# BaseArduino.net
KiCad netlist of a schematic drawn in Altium Designer
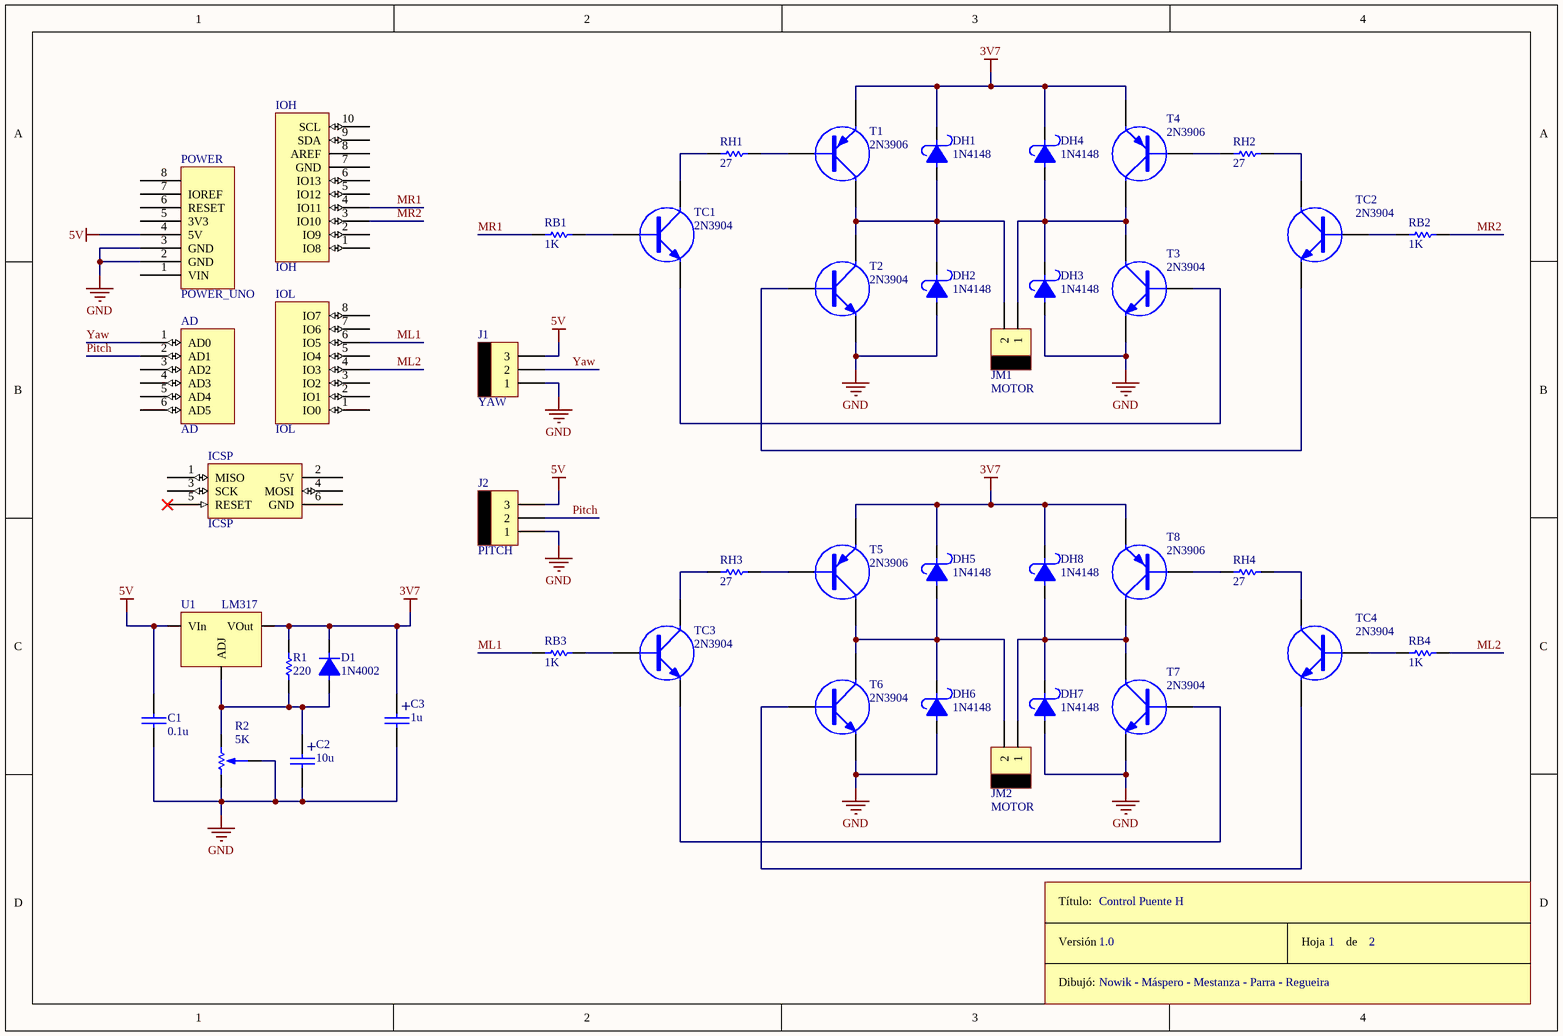
[diagram p0: BaseArduino.SchDoc]

(export (version "E")
  (design (tool "Eeschema 10.0.6"))
  (components
    (comp (ref "AD") (value "AD") (footprint "Header 6x1 8.5mm") (libsource (lib "Headers") (part "AD")))
    (comp (ref "C1") (value "0.1u") (footprint "CAP100") (libsource (lib "LIBEBAL") (part "CAP")))
    (comp (ref "C2") (value "10u") (footprint "CAP100RP") (libsource (lib "LIBEBAL") (part "CAPPOL")))
    (comp (ref "C3") (value "1u") (footprint "CAP100RP") (libsource (lib "LIBEBAL") (part "CAPPOL")))
    (comp (ref "D1") (value "1N4002") (footprint "DO41") (libsource (lib "LIBEBAL") (part "DIODO")))
    (comp (ref "DH1") (value "1N4148") (footprint "DO41") (libsource (lib "LIBEBAL") (part "DIODO SCHOTTKY")))
    (comp (ref "DH2") (value "1N4148") (footprint "DO41") (libsource (lib "LIBEBAL") (part "DIODO SCHOTTKY")))
    (comp (ref "DH3") (value "1N4148") (footprint "DO41") (libsource (lib "LIBEBAL") (part "DIODO SCHOTTKY")))
    (comp (ref "DH4") (value "1N4148") (footprint "DO41") (libsource (lib "LIBEBAL") (part "DIODO SCHOTTKY")))
    (comp (ref "DH5") (value "1N4148") (footprint "DO41") (libsource (lib "LIBEBAL") (part "DIODO SCHOTTKY")))
    (comp (ref "DH6") (value "1N4148") (footprint "DO41") (libsource (lib "LIBEBAL") (part "DIODO SCHOTTKY")))
    (comp (ref "DH7") (value "1N4148") (footprint "DO41") (libsource (lib "LIBEBAL") (part "DIODO SCHOTTKY")))
    (comp (ref "DH8") (value "1N4148") (footprint "DO41") (libsource (lib "LIBEBAL") (part "DIODO SCHOTTKY")))
    (comp (ref "ICSP") (value "ICSP") (footprint "ICSP") (libsource (lib "Headers") (part "ICSP")))
    (comp (ref "IOH") (value "IOH") (footprint "Header 10x1 8.5mm") (libsource (lib "Headers") (part "IOH")))
    (comp (ref "IOL") (value "IOL") (footprint "Header 8x1 8.5mm") (libsource (lib "Headers") (part "IOL")))
    (comp (ref "J1") (value "YAW") (footprint "MOLEX3") (libsource (lib "LIBEBAL") (part "MOLEX3")))
    (comp (ref "J2") (value "PITCH") (footprint "MOLEX3") (libsource (lib "LIBEBAL") (part "MOLEX3")))
    (comp (ref "JM1") (value "MOTOR") (footprint "MOLEX2") (libsource (lib "LIBEBAL") (part "MOLEX2")))
    (comp (ref "JM2") (value "MOTOR") (footprint "MOLEX2") (libsource (lib "LIBEBAL") (part "MOLEX2")))
    (comp (ref "POWER")
      (value "POWER_UNO")
      (footprint "Header 8x1 8.5mm")
      (libsource (lib "Headers") (part "POWER_UNO"))
    )
    (comp (ref "R1") (value "220") (footprint "RES300") (libsource (lib "LIBEBAL") (part "RES")))
    (comp (ref "R2") (value "5K") (footprint "PRESET V") (libsource (lib "LIBEBAL") (part "PRESET")))
    (comp (ref "RB1") (value "1K") (footprint "RES300") (libsource (lib "LIBEBAL") (part "RES")))
    (comp (ref "RB2") (value "1K") (footprint "RES300") (libsource (lib "LIBEBAL") (part "RES")))
    (comp (ref "RB3") (value "1K") (footprint "RES300") (libsource (lib "LIBEBAL") (part "RES")))
    (comp (ref "RB4") (value "1K") (footprint "RES300") (libsource (lib "LIBEBAL") (part "RES")))
    (comp (ref "RH1") (value "27") (footprint "RES300") (libsource (lib "LIBEBAL") (part "RES")))
    (comp (ref "RH2") (value "27") (footprint "RES300") (libsource (lib "LIBEBAL") (part "RES")))
    (comp (ref "RH3") (value "27") (footprint "RES300") (libsource (lib "LIBEBAL") (part "RES")))
    (comp (ref "RH4") (value "27") (footprint "RES300") (libsource (lib "LIBEBAL") (part "RES")))
    (comp (ref "ROT1") (value "Rótulo") (libsource (lib "LIB PIO IX") (part "Rótulo")))
    (comp (ref "T1") (value "2N3906") (footprint "TO92") (libsource (lib "LIBEBAL") (part "TRANSISTOR PNP")))
    (comp (ref "T2")
      (value "2N3904")
      (footprint "LIBEBAL:TO92")
      (libsource (lib "LIBEBAL") (part "TRANSISTOR NPN"))
    )
    (comp (ref "T3")
      (value "2N3904")
      (footprint "LIBEBAL:TO92")
      (libsource (lib "LIBEBAL") (part "TRANSISTOR NPN"))
    )
    (comp (ref "T4")
      (value "2N3906")
      (footprint "LIBEBAL:TO92")
      (libsource (lib "LIBEBAL") (part "TRANSISTOR PNP"))
    )
    (comp (ref "T5") (value "2N3906") (footprint "TO92") (libsource (lib "LIBEBAL") (part "TRANSISTOR PNP")))
    (comp (ref "T6") (value "2N3904") (footprint "TO92") (libsource (lib "LIBEBAL") (part "TRANSISTOR NPN")))
    (comp (ref "T7") (value "2N3904") (footprint "TO92") (libsource (lib "LIBEBAL") (part "TRANSISTOR NPN")))
    (comp (ref "T8") (value "2N3906") (footprint "TO92") (libsource (lib "LIBEBAL") (part "TRANSISTOR PNP")))
    (comp (ref "TC1") (value "2N3904") (footprint "TO92") (libsource (lib "LIBEBAL") (part "TRANSISTOR NPN")))
    (comp (ref "TC2")
      (value "2N3904")
      (footprint "LIBEBAL:TO92")
      (libsource (lib "LIBEBAL") (part "TRANSISTOR NPN"))
    )
    (comp (ref "TC3") (value "2N3904") (footprint "TO92") (libsource (lib "LIBEBAL") (part "TRANSISTOR NPN")))
    (comp (ref "TC4") (value "2N3904") (footprint "TO92") (libsource (lib "LIBEBAL") (part "TRANSISTOR NPN")))
    (comp (ref "U1")
      (value "LM317")
      (footprint "TO-220 V")
      (description "IC REG ADJ 1.5A 3 TERM TO-220")
      (libsource (lib "LIBEBAL") (part "LM317"))
    )
  )
  (nets
    (net (code "1") (name "/ML1") (class "Default")
      (node (ref "IOL") (pin "6") (pinfunction "IO5_6") (pintype "bidirectional"))
      (node (ref "RB3") (pin "1") (pinfunction "1_1") (pintype "passive"))
    )
    (net (code "2") (name "/ML2") (class "Default")
      (node (ref "IOL") (pin "4") (pinfunction "IO3_4") (pintype "bidirectional"))
      (node (ref "RB4") (pin "2") (pinfunction "2_2") (pintype "passive"))
    )
    (net (code "3") (name "/MR1") (class "Default")
      (node (ref "IOH") (pin "4") (pinfunction "IO11_4") (pintype "bidirectional"))
      (node (ref "RB1") (pin "1") (pinfunction "1_1") (pintype "passive"))
    )
    (net (code "4") (name "/MR2") (class "Default")
      (node (ref "IOH") (pin "3") (pinfunction "IO10_3") (pintype "bidirectional"))
      (node (ref "RB2") (pin "2") (pinfunction "2_2") (pintype "passive"))
    )
    (net (code "5") (name "/Pitch") (class "Default")
      (node (ref "AD") (pin "2") (pinfunction "AD1_2") (pintype "bidirectional"))
      (node (ref "J2") (pin "2") (pinfunction "2_2") (pintype "passive"))
    )
    (net (code "6") (name "/Yaw") (class "Default")
      (node (ref "AD") (pin "1") (pinfunction "AD0_1") (pintype "bidirectional"))
      (node (ref "J1") (pin "2") (pinfunction "2_2") (pintype "passive"))
    )
    (net (code "7") (name "3V7") (class "Default")
      (node (ref "C3") (pin "1") (pinfunction "1_1") (pintype "passive"))
      (node (ref "D1") (pin "2") (pinfunction "2_2") (pintype "passive"))
      (node (ref "DH1") (pin "2") (pinfunction "2_2") (pintype "passive"))
      (node (ref "DH4") (pin "2") (pinfunction "2_2") (pintype "passive"))
      (node (ref "DH5") (pin "2") (pinfunction "2_2") (pintype "passive"))
      (node (ref "DH8") (pin "2") (pinfunction "2_2") (pintype "passive"))
      (node (ref "R1") (pin "2") (pinfunction "2_2") (pintype "passive"))
      (node (ref "T1") (pin "3") (pinfunction "E_3") (pintype "passive"))
      (node (ref "T4") (pin "3") (pinfunction "E_3") (pintype "passive"))
      (node (ref "T5") (pin "3") (pinfunction "E_3") (pintype "passive"))
      (node (ref "T8") (pin "3") (pinfunction "E_3") (pintype "passive"))
      (node (ref "U1") (pin "2") (pinfunction "VOut_2") (pintype "passive"))
    )
    (net (code "8") (name "5V") (class "Default")
      (node (ref "C1") (pin "1") (pinfunction "1_1") (pintype "passive"))
      (node (ref "J1") (pin "3") (pinfunction "3_3") (pintype "passive"))
      (node (ref "J2") (pin "3") (pinfunction "3_3") (pintype "passive"))
      (node (ref "POWER") (pin "4") (pinfunction "5V_4") (pintype "power_in"))
      (node (ref "U1") (pin "3") (pinfunction "VIn_3") (pintype "passive"))
    )
    (net (code "9") (name "GND") (class "Default")
      (node (ref "C1") (pin "2") (pinfunction "2_2") (pintype "passive"))
      (node (ref "C2") (pin "2") (pinfunction "2_2") (pintype "passive"))
      (node (ref "C3") (pin "2") (pinfunction "2_2") (pintype "passive"))
      (node (ref "DH2") (pin "1") (pinfunction "1_1") (pintype "passive"))
      (node (ref "DH3") (pin "1") (pinfunction "1_1") (pintype "passive"))
      (node (ref "DH6") (pin "1") (pinfunction "1_1") (pintype "passive"))
      (node (ref "DH7") (pin "1") (pinfunction "1_1") (pintype "passive"))
      (node (ref "J1") (pin "1") (pinfunction "1_1") (pintype "passive"))
      (node (ref "J2") (pin "1") (pinfunction "1_1") (pintype "passive"))
      (node (ref "POWER") (pin "2") (pinfunction "GND_2") (pintype "power_in"))
      (node (ref "POWER") (pin "3") (pinfunction "GND_3") (pintype "power_in"))
      (node (ref "R2") (pin "2") (pinfunction "2_2") (pintype "passive"))
      (node (ref "R2") (pin "3") (pinfunction "3_3") (pintype "passive"))
      (node (ref "T2") (pin "3") (pinfunction "E_3") (pintype "passive"))
      (node (ref "T3") (pin "3") (pinfunction "E_3") (pintype "passive"))
      (node (ref "T6") (pin "3") (pinfunction "E_3") (pintype "passive"))
      (node (ref "T7") (pin "3") (pinfunction "E_3") (pintype "passive"))
    )
    (net (code "10") (name "Net-(T1-B)") (class "Default")
      (node (ref "RH1") (pin "2") (pinfunction "2_2") (pintype "passive"))
      (node (ref "T1") (pin "1") (pinfunction "B_1") (pintype "passive"))
    )
    (net (code "11") (name "Net-(T1-C)") (class "Default")
      (node (ref "DH1") (pin "1") (pinfunction "1_1") (pintype "passive"))
      (node (ref "DH2") (pin "2") (pinfunction "2_2") (pintype "passive"))
      (node (ref "JM1") (pin "2") (pinfunction "2_2") (pintype "passive"))
      (node (ref "T1") (pin "2") (pinfunction "C_2") (pintype "passive"))
      (node (ref "T2") (pin "2") (pinfunction "C_2") (pintype "passive"))
    )
    (net (code "12") (name "Net-(T2-B)") (class "Default")
      (node (ref "T2") (pin "1") (pinfunction "B_1") (pintype "passive"))
      (node (ref "TC2") (pin "3") (pinfunction "E_3") (pintype "passive"))
    )
    (net (code "13") (name "Net-(T3-B)") (class "Default")
      (node (ref "T3") (pin "1") (pinfunction "B_1") (pintype "passive"))
      (node (ref "TC1") (pin "3") (pinfunction "E_3") (pintype "passive"))
    )
    (net (code "14") (name "Net-(T3-C)") (class "Default")
      (node (ref "DH3") (pin "2") (pinfunction "2_2") (pintype "passive"))
      (node (ref "DH4") (pin "1") (pinfunction "1_1") (pintype "passive"))
      (node (ref "JM1") (pin "1") (pinfunction "1_1") (pintype "passive"))
      (node (ref "T3") (pin "2") (pinfunction "C_2") (pintype "passive"))
      (node (ref "T4") (pin "2") (pinfunction "C_2") (pintype "passive"))
    )
    (net (code "15") (name "Net-(T4-B)") (class "Default")
      (node (ref "RH2") (pin "1") (pinfunction "1_1") (pintype "passive"))
      (node (ref "T4") (pin "1") (pinfunction "B_1") (pintype "passive"))
    )
    (net (code "16") (name "Net-(T5-B)") (class "Default")
      (node (ref "RH3") (pin "2") (pinfunction "2_2") (pintype "passive"))
      (node (ref "T5") (pin "1") (pinfunction "B_1") (pintype "passive"))
    )
    (net (code "17") (name "Net-(T5-C)") (class "Default")
      (node (ref "DH5") (pin "1") (pinfunction "1_1") (pintype "passive"))
      (node (ref "DH6") (pin "2") (pinfunction "2_2") (pintype "passive"))
      (node (ref "JM2") (pin "2") (pinfunction "2_2") (pintype "passive"))
      (node (ref "T5") (pin "2") (pinfunction "C_2") (pintype "passive"))
      (node (ref "T6") (pin "2") (pinfunction "C_2") (pintype "passive"))
    )
    (net (code "18") (name "Net-(T6-B)") (class "Default")
      (node (ref "T6") (pin "1") (pinfunction "B_1") (pintype "passive"))
      (node (ref "TC4") (pin "3") (pinfunction "E_3") (pintype "passive"))
    )
    (net (code "19") (name "Net-(T7-B)") (class "Default")
      (node (ref "T7") (pin "1") (pinfunction "B_1") (pintype "passive"))
      (node (ref "TC3") (pin "3") (pinfunction "E_3") (pintype "passive"))
    )
    (net (code "20") (name "Net-(T7-C)") (class "Default")
      (node (ref "DH7") (pin "2") (pinfunction "2_2") (pintype "passive"))
      (node (ref "DH8") (pin "1") (pinfunction "1_1") (pintype "passive"))
      (node (ref "JM2") (pin "1") (pinfunction "1_1") (pintype "passive"))
      (node (ref "T7") (pin "2") (pinfunction "C_2") (pintype "passive"))
      (node (ref "T8") (pin "2") (pinfunction "C_2") (pintype "passive"))
    )
    (net (code "21") (name "Net-(T8-B)") (class "Default")
      (node (ref "RH4") (pin "1") (pinfunction "1_1") (pintype "passive"))
      (node (ref "T8") (pin "1") (pinfunction "B_1") (pintype "passive"))
    )
    (net (code "22") (name "Net-(TC1-B)") (class "Default")
      (node (ref "RB1") (pin "2") (pinfunction "2_2") (pintype "passive"))
      (node (ref "TC1") (pin "1") (pinfunction "B_1") (pintype "passive"))
    )
    (net (code "23") (name "Net-(TC1-C)") (class "Default")
      (node (ref "RH1") (pin "1") (pinfunction "1_1") (pintype "passive"))
      (node (ref "TC1") (pin "2") (pinfunction "C_2") (pintype "passive"))
    )
    (net (code "24") (name "Net-(TC2-B)") (class "Default")
      (node (ref "RB2") (pin "1") (pinfunction "1_1") (pintype "passive"))
      (node (ref "TC2") (pin "1") (pinfunction "B_1") (pintype "passive"))
    )
    (net (code "25") (name "Net-(TC2-C)") (class "Default")
      (node (ref "RH2") (pin "2") (pinfunction "2_2") (pintype "passive"))
      (node (ref "TC2") (pin "2") (pinfunction "C_2") (pintype "passive"))
    )
    (net (code "26") (name "Net-(TC3-B)") (class "Default")
      (node (ref "RB3") (pin "2") (pinfunction "2_2") (pintype "passive"))
      (node (ref "TC3") (pin "1") (pinfunction "B_1") (pintype "passive"))
    )
    (net (code "27") (name "Net-(TC3-C)") (class "Default")
      (node (ref "RH3") (pin "1") (pinfunction "1_1") (pintype "passive"))
      (node (ref "TC3") (pin "2") (pinfunction "C_2") (pintype "passive"))
    )
    (net (code "28") (name "Net-(TC4-B)") (class "Default")
      (node (ref "RB4") (pin "1") (pinfunction "1_1") (pintype "passive"))
      (node (ref "TC4") (pin "1") (pinfunction "B_1") (pintype "passive"))
    )
    (net (code "29") (name "Net-(TC4-C)") (class "Default")
      (node (ref "RH4") (pin "2") (pinfunction "2_2") (pintype "passive"))
      (node (ref "TC4") (pin "2") (pinfunction "C_2") (pintype "passive"))
    )
    (net (code "30") (name "Net-(U1-ADJ)") (class "Default")
      (node (ref "C2") (pin "1") (pinfunction "1_1") (pintype "passive"))
      (node (ref "D1") (pin "1") (pinfunction "1_1") (pintype "passive"))
      (node (ref "R1") (pin "1") (pinfunction "1_1") (pintype "passive"))
      (node (ref "R2") (pin "1") (pinfunction "1_1") (pintype "passive"))
      (node (ref "U1") (pin "1") (pinfunction "ADJ_1") (pintype "passive"))
    )
    (net (code "31") (name "unconnected-(AD-AD2-Pad3)") (class "Default")
      (node (ref "AD") (pin "3") (pinfunction "AD2_3") (pintype "bidirectional"))
    )
    (net (code "32") (name "unconnected-(AD-AD3-Pad4)") (class "Default")
      (node (ref "AD") (pin "4") (pinfunction "AD3_4") (pintype "bidirectional"))
    )
    (net (code "33") (name "unconnected-(AD-AD4-Pad5)") (class "Default")
      (node (ref "AD") (pin "5") (pinfunction "AD4_5") (pintype "bidirectional"))
    )
    (net (code "34") (name "unconnected-(AD-AD5-Pad6)") (class "Default")
      (node (ref "AD") (pin "6") (pinfunction "AD5_6") (pintype "bidirectional"))
    )
    (net (code "35") (name "unconnected-(ICSP-5V-Pad2)") (class "Default")
      (node (ref "ICSP") (pin "2") (pinfunction "5V_2") (pintype "power_in"))
    )
    (net (code "36") (name "unconnected-(ICSP-GND-Pad6)") (class "Default")
      (node (ref "ICSP") (pin "6") (pinfunction "GND_6") (pintype "power_in"))
    )
    (net (code "37") (name "unconnected-(ICSP-MISO-Pad1)") (class "Default")
      (node (ref "ICSP") (pin "1") (pinfunction "MISO_1") (pintype "bidirectional"))
    )
    (net (code "38") (name "unconnected-(ICSP-MOSI-Pad4)") (class "Default")
      (node (ref "ICSP") (pin "4") (pinfunction "MOSI_4") (pintype "bidirectional"))
    )
    (net (code "39") (name "unconnected-(ICSP-RESET-Pad5)") (class "Default")
      (node (ref "ICSP") (pin "5") (pinfunction "RESET_5") (pintype "input+no_connect"))
    )
    (net (code "40") (name "unconnected-(ICSP-SCK-Pad3)") (class "Default")
      (node (ref "ICSP") (pin "3") (pinfunction "SCK_3") (pintype "bidirectional"))
    )
    (net (code "41") (name "unconnected-(IOH-AREF-Pad8)") (class "Default")
      (node (ref "IOH") (pin "8") (pinfunction "AREF_8") (pintype "passive"))
    )
    (net (code "42") (name "unconnected-(IOH-GND-Pad7)") (class "Default")
      (node (ref "IOH") (pin "7") (pinfunction "GND_7") (pintype "power_in"))
    )
    (net (code "43") (name "unconnected-(IOH-IO8-Pad1)") (class "Default")
      (node (ref "IOH") (pin "1") (pinfunction "IO8_1") (pintype "bidirectional"))
    )
    (net (code "44") (name "unconnected-(IOH-IO9-Pad2)") (class "Default")
      (node (ref "IOH") (pin "2") (pinfunction "IO9_2") (pintype "bidirectional"))
    )
    (net (code "45") (name "unconnected-(IOH-IO12-Pad5)") (class "Default")
      (node (ref "IOH") (pin "5") (pinfunction "IO12_5") (pintype "bidirectional"))
    )
    (net (code "46") (name "unconnected-(IOH-IO13-Pad6)") (class "Default")
      (node (ref "IOH") (pin "6") (pinfunction "IO13_6") (pintype "bidirectional"))
    )
    (net (code "47") (name "unconnected-(IOH-SCL-Pad10)") (class "Default")
      (node (ref "IOH") (pin "10") (pinfunction "SCL_10") (pintype "bidirectional"))
    )
    (net (code "48") (name "unconnected-(IOH-SDA-Pad9)") (class "Default")
      (node (ref "IOH") (pin "9") (pinfunction "SDA_9") (pintype "bidirectional"))
    )
    (net (code "49") (name "unconnected-(IOL-IO0-Pad1)") (class "Default")
      (node (ref "IOL") (pin "1") (pinfunction "IO0_1") (pintype "bidirectional"))
    )
    (net (code "50") (name "unconnected-(IOL-IO1-Pad2)") (class "Default")
      (node (ref "IOL") (pin "2") (pinfunction "IO1_2") (pintype "bidirectional"))
    )
    (net (code "51") (name "unconnected-(IOL-IO2-Pad3)") (class "Default")
      (node (ref "IOL") (pin "3") (pinfunction "IO2_3") (pintype "bidirectional"))
    )
    (net (code "52") (name "unconnected-(IOL-IO4-Pad5)") (class "Default")
      (node (ref "IOL") (pin "5") (pinfunction "IO4_5") (pintype "bidirectional"))
    )
    (net (code "53") (name "unconnected-(IOL-IO6-Pad7)") (class "Default")
      (node (ref "IOL") (pin "7") (pinfunction "IO6_7") (pintype "bidirectional"))
    )
    (net (code "54") (name "unconnected-(IOL-IO7-Pad8)") (class "Default")
      (node (ref "IOL") (pin "8") (pinfunction "IO7_8") (pintype "bidirectional"))
    )
    (net (code "55") (name "unconnected-(POWER-3V3-Pad5)") (class "Default")
      (node (ref "POWER") (pin "5") (pinfunction "3V3_5") (pintype "power_in"))
    )
    (net (code "56") (name "unconnected-(POWER-IOREF-Pad7)") (class "Default")
      (node (ref "POWER") (pin "7") (pinfunction "IOREF_7") (pintype "power_in"))
    )
    (net (code "57") (name "unconnected-(POWER-Pad8)") (class "Default")
      (node (ref "POWER") (pin "8") (pintype "passive"))
    )
    (net (code "58") (name "unconnected-(POWER-RESET-Pad6)") (class "Default")
      (node (ref "POWER") (pin "6") (pinfunction "RESET_6") (pintype "passive"))
    )
    (net (code "59") (name "unconnected-(POWER-VIN-Pad1)") (class "Default")
      (node (ref "POWER") (pin "1") (pinfunction "VIN_1") (pintype "power_in"))
    )
  )
)
